# ais_rx1_v1.net
KiCad netlist of a schematic drawn in EAGLE
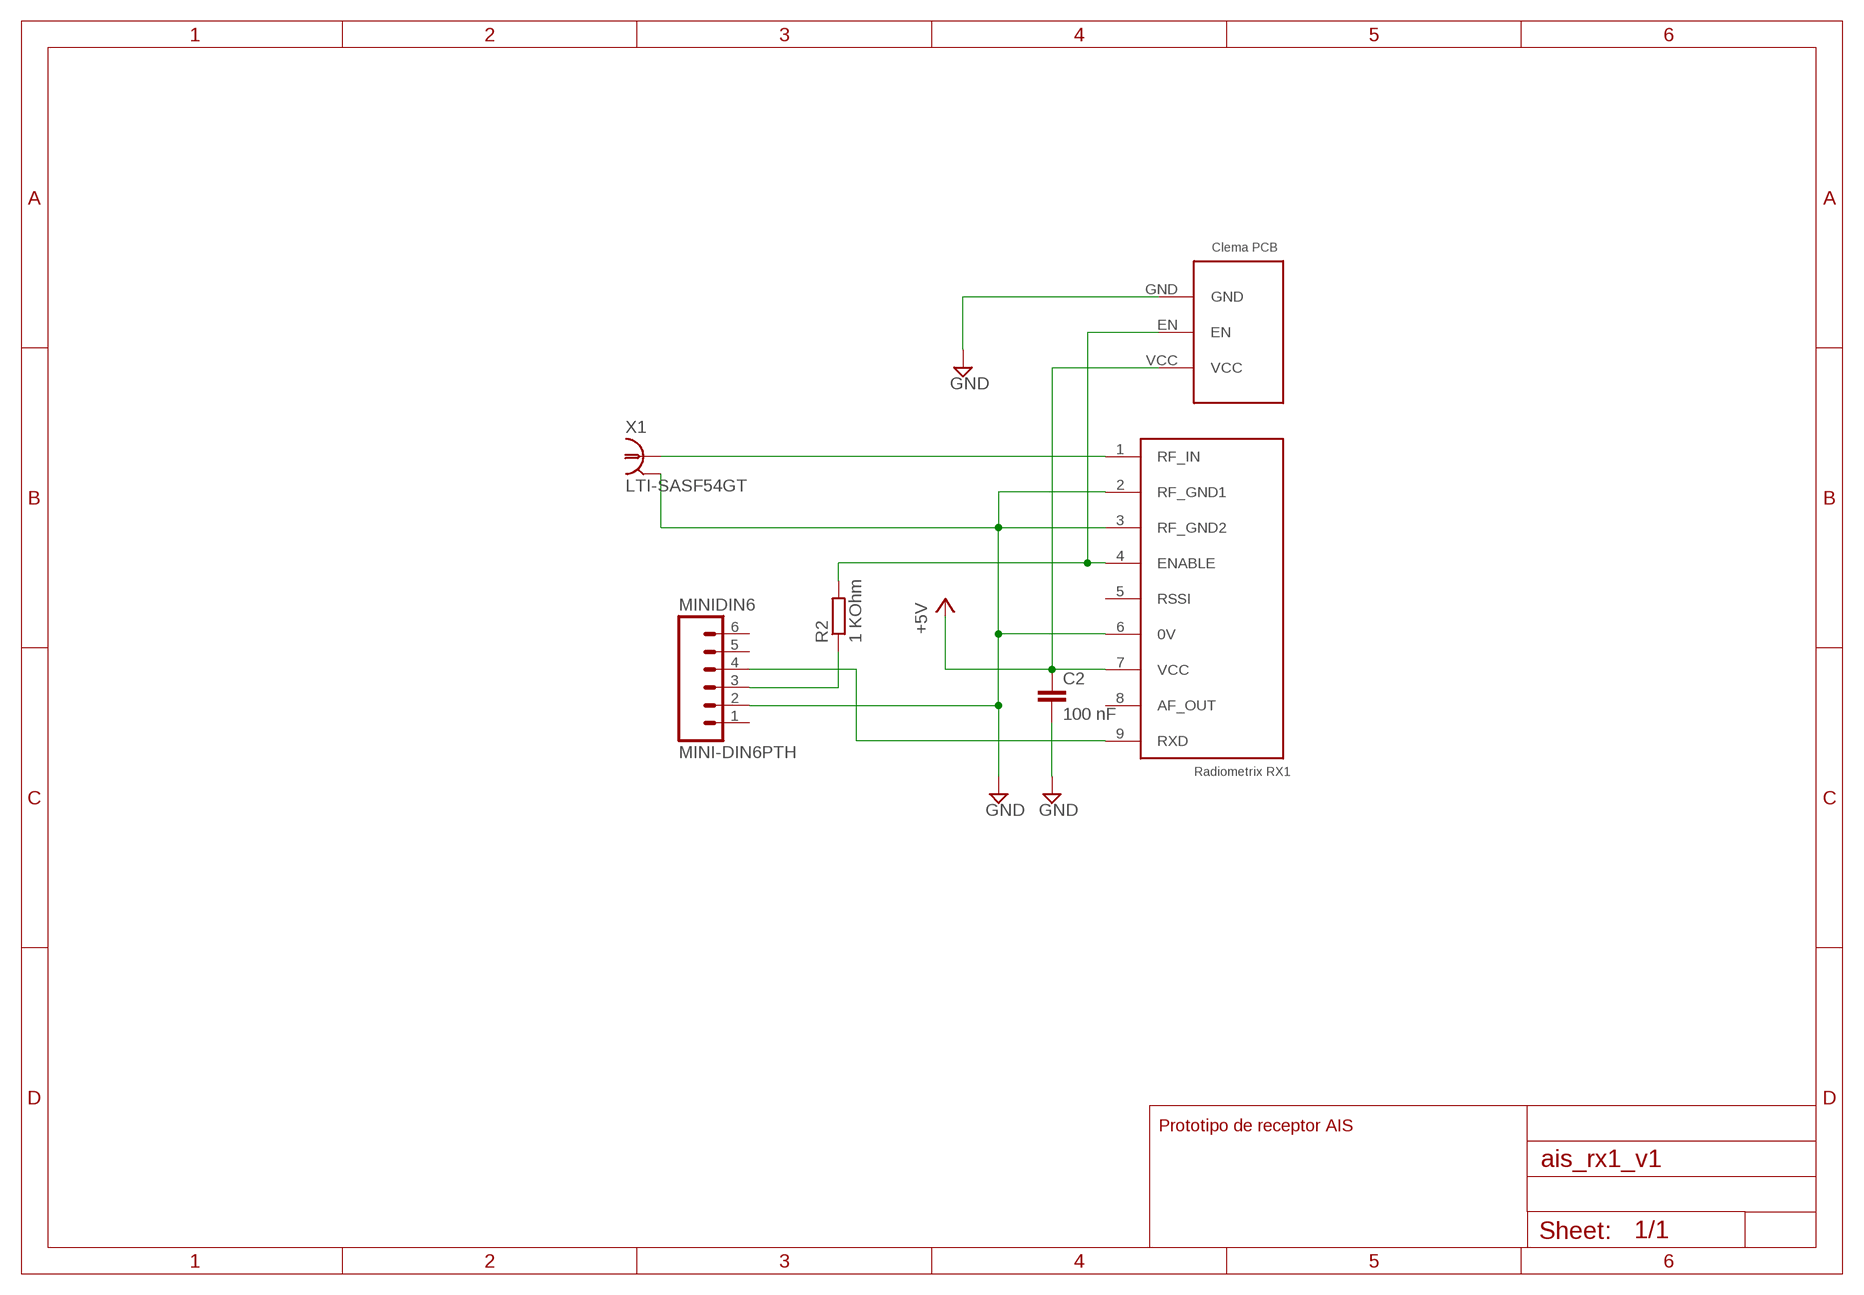
[diagram p0: schematic, sheet 1]

(export (version "E")
  (design (tool "Eeschema 10.0.6"))
  (components
    (comp (ref "C2")
      (value "100 nF")
      (footprint "eagle-import:C0805")
      (libsource (lib "eagle-import") (part "C-EUC0805"))
    )
    (comp (ref "CLEMAPCB1")
      (value "CLEMA")
      (footprint "eagle-import:CLEMA")
      (libsource (lib "eagle-import") (part "CLEMA"))
    )
    (comp (ref "MINIDIN6")
      (value "MINI-DIN6PTH")
      (footprint "eagle-import:MINI-DIN6")
      (libsource (lib "eagle-import") (part "MINI-DIN6PTH"))
    )
    (comp (ref "R2")
      (value "1 KOhm")
      (footprint "eagle-import:R0805")
      (libsource (lib "eagle-import") (part "R-EU_R0805"))
    )
    (comp (ref "RX1")
      (value "RX1")
      (footprint "eagle-import:RX1")
      (libsource (lib "eagle-import") (part "RX1"))
    )
    (comp (ref "X1")
      (value "LTI-SASF54GT")
      (footprint "eagle-import:LTI-SASF54GT")
      (libsource (lib "eagle-import") (part "LTI-SASF54GT"))
    )
  )
  (nets
    (net (code "1") (name "+5V") (class "Default")
      (node (ref "C2") (pin "1") (pinfunction "1_1") (pintype "passive"))
      (node (ref "CLEMAPCB1") (pin "VCC") (pinfunction "VCC_VCC") (pintype "bidirectional"))
      (node (ref "RX1") (pin "7") (pinfunction "VCC_7") (pintype "power_in"))
    )
    (net (code "2") (name "/RSSI") (class "Default")
      (node (ref "RX1") (pin "5") (pinfunction "RSSI_5") (pintype "power_in"))
    )
    (net (code "3") (name "GND") (class "Default")
      (node (ref "C2") (pin "2") (pinfunction "2_2") (pintype "passive"))
      (node (ref "CLEMAPCB1") (pin "GND") (pinfunction "GND_GND") (pintype "bidirectional"))
      (node (ref "MINIDIN6") (pin "2") (pinfunction "2_2") (pintype "passive"))
      (node (ref "RX1") (pin "2") (pinfunction "RF_GND1_2") (pintype "power_in"))
      (node (ref "RX1") (pin "3") (pinfunction "RF_GND2_3") (pintype "power_in"))
      (node (ref "RX1") (pin "6") (pinfunction "0V_6") (pintype "output"))
      (node (ref "X1") (pin "2") (pinfunction "2_2") (pintype "passive"))
      (node (ref "X1") (pin "3") (pinfunction "2_3") (pintype "passive"))
      (node (ref "X1") (pin "4") (pinfunction "2_4") (pintype "passive"))
      (node (ref "X1") (pin "5") (pinfunction "2_5") (pintype "passive"))
    )
    (net (code "4") (name "Net-(MINIDIN6-Pad3)") (class "Default")
      (node (ref "MINIDIN6") (pin "3") (pinfunction "3_3") (pintype "passive"))
      (node (ref "R2") (pin "1") (pinfunction "1_1") (pintype "passive"))
    )
    (net (code "5") (name "Net-(RX1-ENABLE)") (class "Default")
      (node (ref "CLEMAPCB1") (pin "EN") (pinfunction "EN_EN") (pintype "bidirectional"))
      (node (ref "R2") (pin "2") (pinfunction "2_2") (pintype "passive"))
      (node (ref "RX1") (pin "4") (pinfunction "ENABLE_4") (pintype "input"))
    )
    (net (code "6") (name "Net-(RX1-RF_IN)") (class "Default")
      (node (ref "RX1") (pin "1") (pinfunction "RF_IN_1") (pintype "input"))
      (node (ref "X1") (pin "1") (pinfunction "1_1") (pintype "passive"))
    )
    (net (code "7") (name "Net-(RX1-RXD)") (class "Default")
      (node (ref "MINIDIN6") (pin "4") (pinfunction "4_4") (pintype "passive"))
      (node (ref "RX1") (pin "9") (pinfunction "RXD_9") (pintype "output"))
    )
    (net (code "8") (name "unconnected-(MINIDIN6-Pad1)") (class "Default")
      (node (ref "MINIDIN6") (pin "1") (pinfunction "1_1") (pintype "passive"))
    )
    (net (code "9") (name "unconnected-(MINIDIN6-Pad5)") (class "Default")
      (node (ref "MINIDIN6") (pin "5") (pinfunction "5_5") (pintype "passive"))
    )
    (net (code "10") (name "unconnected-(MINIDIN6-Pad6)") (class "Default")
      (node (ref "MINIDIN6") (pin "6") (pinfunction "6_6") (pintype "passive"))
    )
    (net (code "11") (name "unconnected-(RX1-AF_OUT-Pad8)") (class "Default")
      (node (ref "RX1") (pin "8") (pinfunction "AF_OUT_8") (pintype "output"))
    )
  )
)
